# Master.net
KiCad netlist of a schematic drawn in Altium Designer
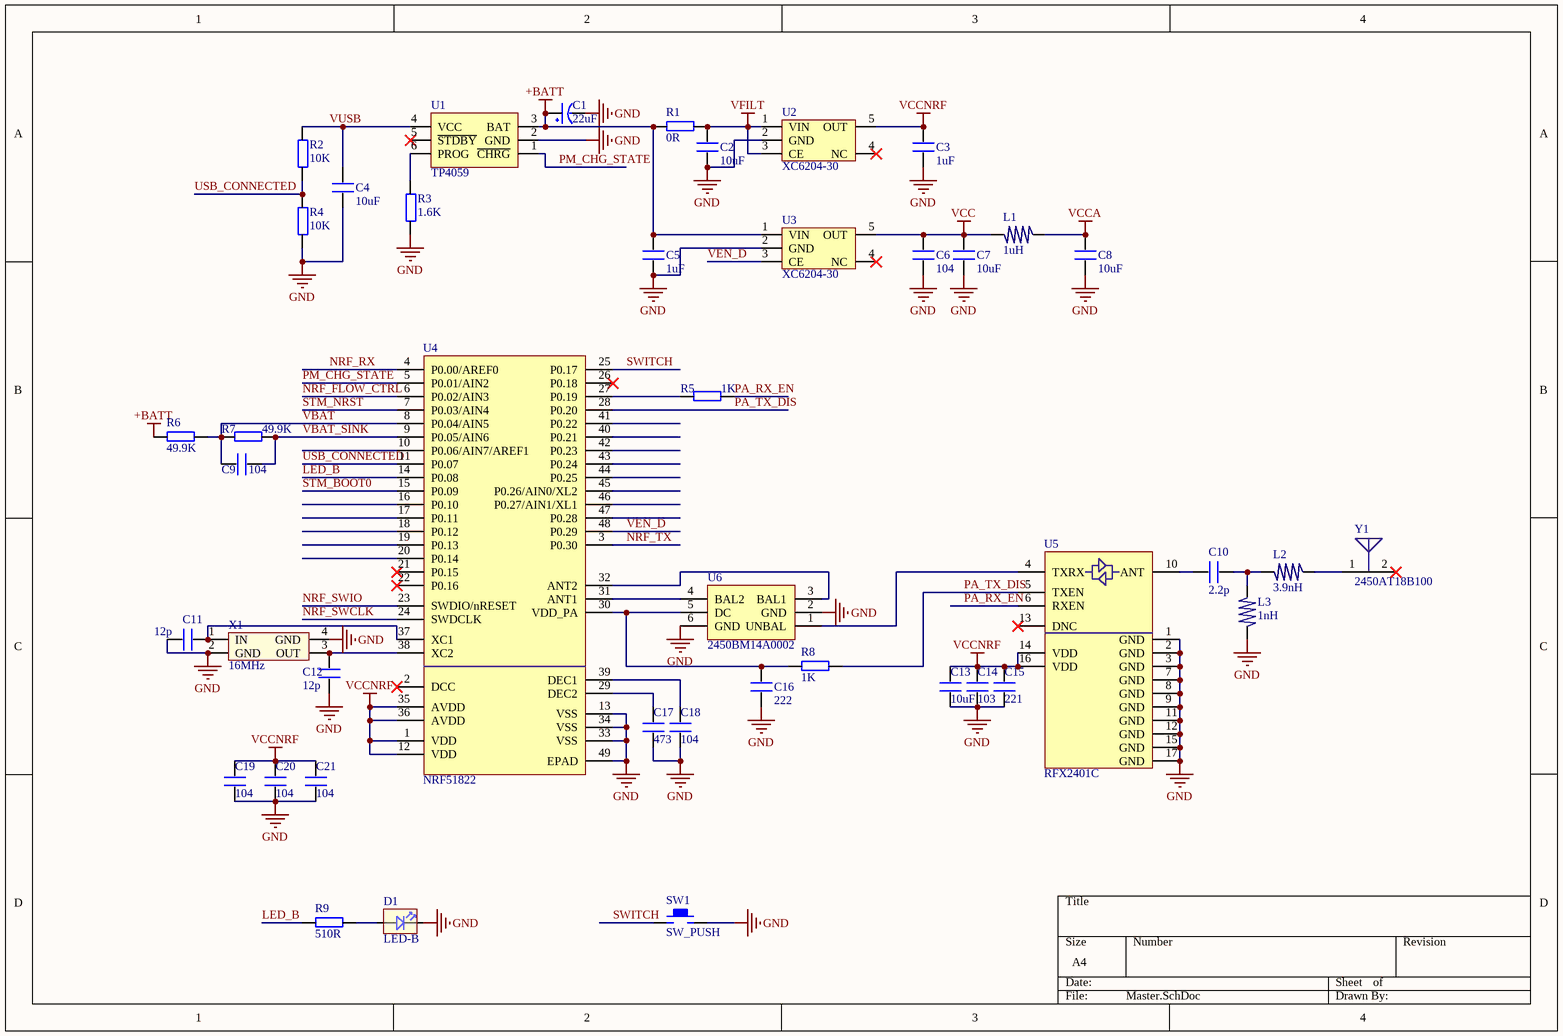
[diagram p0: Master.SchDoc]

(export (version "E")
  (design (tool "Eeschema 10.0.6"))
  (components
    (comp (ref "C1") (value "22uF") (footprint "C0805 钽电容") (libsource (lib "MiniFly ") (part "CAP")))
    (comp (ref "C2") (value "10uF") (footprint "0603P") (libsource (lib "MiniFly ") (part "C")))
    (comp (ref "C3") (value "1uF") (footprint "0402") (libsource (lib "MiniFly ") (part "C")))
    (comp (ref "C4") (value "10uF") (footprint "0603P") (libsource (lib "MiniFly ") (part "C")))
    (comp (ref "C5") (value "1uF") (footprint "0402") (libsource (lib "MiniFly ") (part "C")))
    (comp (ref "C6") (value "104") (footprint "0402") (libsource (lib "MiniFly ") (part "C")))
    (comp (ref "C7") (value "10uF") (footprint "0603P") (libsource (lib "MiniFly ") (part "C")))
    (comp (ref "C8") (value "10uF") (footprint "0603P") (libsource (lib "MiniFly ") (part "C")))
    (comp (ref "C9") (value "104") (footprint "0402") (libsource (lib "MiniFly ") (part "C")))
    (comp (ref "C10") (value "2.2p") (footprint "0402") (libsource (lib "MiniFly ") (part "C")))
    (comp (ref "C11") (value "12p") (footprint "0402") (libsource (lib "MiniFly ") (part "C")))
    (comp (ref "C12") (value "12p") (footprint "0402") (libsource (lib "MiniFly ") (part "C")))
    (comp (ref "C13") (value "10uF") (footprint "0603P") (libsource (lib "MiniFly ") (part "C")))
    (comp (ref "C14") (value "103") (footprint "0402") (libsource (lib "MiniFly ") (part "C")))
    (comp (ref "C15") (value "221") (footprint "0402") (libsource (lib "MiniFly ") (part "C")))
    (comp (ref "C16") (value "222") (footprint "0402") (libsource (lib "MiniFly ") (part "C")))
    (comp (ref "C17") (value "473") (footprint "0402") (libsource (lib "MiniFly ") (part "C")))
    (comp (ref "C18") (value "104") (footprint "0402") (libsource (lib "MiniFly ") (part "C")))
    (comp (ref "C19") (value "104") (footprint "0402") (libsource (lib "MiniFly ") (part "C")))
    (comp (ref "C20") (value "104") (footprint "0402") (libsource (lib "MiniFly ") (part "C")))
    (comp (ref "C21") (value "104") (footprint "0402") (libsource (lib "MiniFly ") (part "C")))
    (comp (ref "D1")
      (value "LED-B")
      (footprint "LED1206  侧贴")
      (description "LED 1206 侧贴  单色")
      (libsource (lib "MiniFly ") (part "LED 1206 侧贴  单色"))
    )
    (comp (ref "L1") (value "1uH") (footprint "0603P") (libsource (lib "") (part "L_1")))
    (comp (ref "L2") (value "3.9nH") (footprint "0603P") (libsource (lib "") (part "L_1")))
    (comp (ref "L3") (value "1nH") (footprint "0603P") (libsource (lib "MiniFly ") (part "L")))
    (comp (ref "R1") (value "0R") (footprint "0402") (libsource (lib "MiniFly ") (part "R")))
    (comp (ref "R2") (value "10K") (footprint "0402") (libsource (lib "MiniFly ") (part "R")))
    (comp (ref "R3") (value "1.6K") (footprint "0402") (libsource (lib "MiniFly ") (part "R")))
    (comp (ref "R4") (value "10K") (footprint "0402") (libsource (lib "MiniFly ") (part "R")))
    (comp (ref "R5") (value "1K") (footprint "0402") (libsource (lib "MiniFly ") (part "R")))
    (comp (ref "R6") (value "49.9K") (footprint "0402") (libsource (lib "MiniFly ") (part "R")))
    (comp (ref "R7") (value "49.9K") (footprint "0402") (libsource (lib "MiniFly ") (part "R")))
    (comp (ref "R8") (value "1K") (footprint "0402") (libsource (lib "MiniFly ") (part "R")))
    (comp (ref "R9") (value "510R") (footprint "0402") (libsource (lib "MiniFly ") (part "R")))
    (comp (ref "SW1") (value "SW_PUSH") (footprint "KEY_2S") (libsource (lib "MiniFly ") (part "KEY")))
    (comp (ref "U1") (value "TP4059") (footprint "SOT23-6S") (libsource (lib "MiniFly ") (part "TP4059")))
    (comp (ref "U2") (value "XC6204-30") (footprint "SOT23-5S") (libsource (lib "MiniFly ") (part "XC6204")))
    (comp (ref "U3") (value "XC6204-30") (footprint "SOT23-5S") (libsource (lib "MiniFly ") (part "XC6204")))
    (comp (ref "U4")
      (value "NRF51822")
      (footprint "QFN48M-04")
      (libsource (lib "MiniFly ") (part "NRF51822"))
    )
    (comp (ref "U5") (value "RFX2401C") (footprint "QFN16M") (libsource (lib "MiniFly ") (part "RFX2401C")))
    (comp (ref "U6") (value "2450BM14A0002") (footprint "0603-6") (libsource (lib "MiniFly ") (part "BALUN")))
    (comp (ref "X1")
      (value "16MHz")
      (footprint "XTAL3225   无源")
      (description "无源贴片晶振")
      (libsource (lib "MiniFly ") (part "XTAL-无源贴片"))
    )
    (comp (ref "Y1")
      (value "2450AT18B100")
      (footprint "1206")
      (libsource (lib "MiniFly ") (part "CHIP_ANTENNA"))
    )
  )
  (nets
    (net (code "1") (name "+BATT") (class "Default")
      (node (ref "C1") (pin "1") (pinfunction "VCC_1") (pintype "passive"))
      (node (ref "C5") (pin "2") (pintype "passive"))
      (node (ref "R1") (pin "2") (pintype "passive"))
      (node (ref "R6") (pin "2") (pintype "passive"))
      (node (ref "U1") (pin "3") (pinfunction "BAT_3") (pintype "passive"))
      (node (ref "U3") (pin "1") (pinfunction "VIN_1") (pintype "passive"))
    )
    (net (code "2") (name "/LED_B") (class "Default")
      (node (ref "R9") (pin "2") (pintype "passive"))
      (node (ref "U4") (pin "14") (pinfunction "P0.08_14") (pintype "passive"))
    )
    (net (code "3") (name "/NRF_FLOW_CTRL") (class "Default")
      (node (ref "U4") (pin "6") (pinfunction "P0.02/AIN3_6") (pintype "passive"))
    )
    (net (code "4") (name "/NRF_RX") (class "Default")
      (node (ref "U4") (pin "4") (pinfunction "P0.00/AREF0_4") (pintype "passive"))
    )
    (net (code "5") (name "/NRF_SWCLK") (class "Default")
      (node (ref "U4") (pin "24") (pinfunction "SWDCLK_24") (pintype "passive"))
    )
    (net (code "6") (name "/NRF_SWIO") (class "Default")
      (node (ref "U4") (pin "23") (pinfunction "SWDIO/nRESET_23") (pintype "passive"))
    )
    (net (code "7") (name "/NRF_TX") (class "Default")
      (node (ref "U4") (pin "3") (pinfunction "P0.30_3") (pintype "passive"))
    )
    (net (code "8") (name "/PA_RX_EN") (class "Default")
      (node (ref "R5") (pin "1") (pintype "passive"))
      (node (ref "U5") (pin "6") (pinfunction "RXEN_6") (pintype "passive"))
    )
    (net (code "9") (name "/PA_TX_DIS") (class "Default")
      (node (ref "R8") (pin "1") (pintype "passive"))
      (node (ref "U4") (pin "28") (pinfunction "P0.20_28") (pintype "passive"))
      (node (ref "U5") (pin "5") (pinfunction "TXEN_5") (pintype "passive"))
    )
    (net (code "10") (name "/PM_CHG_STATE") (class "Default")
      (node (ref "U1") (pin "1") (pinfunction "~{CHRG}_1") (pintype "passive"))
      (node (ref "U4") (pin "5") (pinfunction "P0.01/AIN2_5") (pintype "passive"))
    )
    (net (code "11") (name "/STM_BOOT0") (class "Default")
      (node (ref "U4") (pin "15") (pinfunction "P0.09_15") (pintype "passive"))
    )
    (net (code "12") (name "/STM_NRST") (class "Default")
      (node (ref "U4") (pin "7") (pinfunction "P0.03/AIN4_7") (pintype "passive"))
    )
    (net (code "13") (name "/SWITCH") (class "Default")
      (node (ref "SW1") (pin "1") (pinfunction "1_1") (pintype "passive"))
      (node (ref "U4") (pin "25") (pinfunction "P0.17_25") (pintype "passive"))
    )
    (net (code "14") (name "/USB_CONNECTED") (class "Default")
      (node (ref "R2") (pin "1") (pintype "passive"))
      (node (ref "R4") (pin "2") (pintype "passive"))
      (node (ref "U4") (pin "11") (pinfunction "P0.07_11") (pintype "passive"))
    )
    (net (code "15") (name "/VBAT") (class "Default")
      (node (ref "C9") (pin "2") (pintype "passive"))
      (node (ref "R6") (pin "1") (pintype "passive"))
      (node (ref "R7") (pin "2") (pintype "passive"))
      (node (ref "U4") (pin "8") (pinfunction "P0.04/AIN5_8") (pintype "passive"))
    )
    (net (code "16") (name "/VBAT_SINK") (class "Default")
      (node (ref "C9") (pin "1") (pintype "passive"))
      (node (ref "R7") (pin "1") (pintype "passive"))
      (node (ref "U4") (pin "9") (pinfunction "P0.05/AIN6_9") (pintype "passive"))
    )
    (net (code "17") (name "/VEN_D") (class "Default")
      (node (ref "U3") (pin "3") (pinfunction "CE_3") (pintype "passive"))
      (node (ref "U4") (pin "48") (pinfunction "P0.29_48") (pintype "passive"))
    )
    (net (code "18") (name "/VUSB") (class "Default")
      (node (ref "C4") (pin "2") (pintype "passive"))
      (node (ref "R2") (pin "2") (pintype "passive"))
      (node (ref "U1") (pin "4") (pinfunction "VCC_4") (pintype "passive"))
    )
    (net (code "19") (name "GND") (class "Default")
      (node (ref "C1") (pin "2") (pinfunction "GND_2") (pintype "passive"))
      (node (ref "C11") (pin "2") (pintype "passive"))
      (node (ref "C12") (pin "2") (pintype "passive"))
      (node (ref "C13") (pin "2") (pintype "passive"))
      (node (ref "C14") (pin "2") (pintype "passive"))
      (node (ref "C15") (pin "2") (pintype "passive"))
      (node (ref "C16") (pin "2") (pintype "passive"))
      (node (ref "C17") (pin "2") (pintype "passive"))
      (node (ref "C18") (pin "2") (pintype "passive"))
      (node (ref "C19") (pin "2") (pintype "passive"))
      (node (ref "C2") (pin "1") (pintype "passive"))
      (node (ref "C20") (pin "2") (pintype "passive"))
      (node (ref "C21") (pin "2") (pintype "passive"))
      (node (ref "C3") (pin "1") (pintype "passive"))
      (node (ref "C4") (pin "1") (pintype "passive"))
      (node (ref "C5") (pin "1") (pintype "passive"))
      (node (ref "C6") (pin "1") (pintype "passive"))
      (node (ref "C7") (pin "1") (pintype "passive"))
      (node (ref "C8") (pin "1") (pintype "passive"))
      (node (ref "D1") (pin "1") (pinfunction "1_1") (pintype "passive"))
      (node (ref "L3") (pin "2") (pintype "passive"))
      (node (ref "R3") (pin "1") (pintype "passive"))
      (node (ref "R4") (pin "1") (pintype "passive"))
      (node (ref "SW1") (pin "2") (pinfunction "2_2") (pintype "passive"))
      (node (ref "U1") (pin "2") (pinfunction "GND_2") (pintype "passive"))
      (node (ref "U2") (pin "2") (pinfunction "GND_2") (pintype "passive"))
      (node (ref "U3") (pin "2") (pinfunction "GND_2") (pintype "passive"))
      (node (ref "U4") (pin "13") (pinfunction "VSS_13") (pintype "passive"))
      (node (ref "U4") (pin "33") (pinfunction "VSS_33") (pintype "passive"))
      (node (ref "U4") (pin "34") (pinfunction "VSS_34") (pintype "passive"))
      (node (ref "U4") (pin "49") (pinfunction "EPAD_49") (pintype "passive"))
      (node (ref "U5") (pin "1") (pinfunction "GND_1") (pintype "passive"))
      (node (ref "U5") (pin "11") (pinfunction "GND_11") (pintype "passive"))
      (node (ref "U5") (pin "12") (pinfunction "GND_12") (pintype "passive"))
      (node (ref "U5") (pin "15") (pinfunction "GND_15") (pintype "passive"))
      (node (ref "U5") (pin "17") (pinfunction "GND_17") (pintype "passive"))
      (node (ref "U5") (pin "2") (pinfunction "GND_2") (pintype "passive"))
      (node (ref "U5") (pin "3") (pinfunction "GND_3") (pintype "passive"))
      (node (ref "U5") (pin "7") (pinfunction "GND_7") (pintype "passive"))
      (node (ref "U5") (pin "8") (pinfunction "GND_8") (pintype "passive"))
      (node (ref "U5") (pin "9") (pinfunction "GND_9") (pintype "passive"))
      (node (ref "U6") (pin "2") (pinfunction "GND_2") (pintype "passive"))
      (node (ref "U6") (pin "6") (pinfunction "GND_6") (pintype "passive"))
      (node (ref "X1") (pin "2") (pinfunction "GND_2") (pintype "passive"))
      (node (ref "X1") (pin "4") (pinfunction "GND_4") (pintype "passive"))
    )
    (net (code "20") (name "Net-(C10-Pad2)") (class "Default")
      (node (ref "C10") (pin "2") (pintype "passive"))
      (node (ref "L2") (pin "2") (pintype "passive"))
      (node (ref "L3") (pin "1") (pintype "passive"))
    )
    (net (code "21") (name "Net-(D1-Pad3)") (class "Default")
      (node (ref "D1") (pin "3") (pinfunction "3_3") (pintype "passive"))
      (node (ref "R9") (pin "1") (pintype "passive"))
    )
    (net (code "22") (name "Net-(U1-PROG)") (class "Default")
      (node (ref "R3") (pin "2") (pintype "passive"))
      (node (ref "U1") (pin "6") (pinfunction "PROG_6") (pintype "passive"))
    )
    (net (code "23") (name "Net-(U4-ANT1)") (class "Default")
      (node (ref "U4") (pin "31") (pinfunction "ANT1_31") (pintype "passive"))
      (node (ref "U6") (pin "4") (pinfunction "BAL2_4") (pintype "passive"))
    )
    (net (code "24") (name "Net-(U4-ANT2)") (class "Default")
      (node (ref "U4") (pin "32") (pinfunction "ANT2_32") (pintype "passive"))
      (node (ref "U6") (pin "3") (pinfunction "BAL1_3") (pintype "passive"))
    )
    (net (code "25") (name "Net-(U4-DEC1)") (class "Default")
      (node (ref "C18") (pin "1") (pintype "passive"))
      (node (ref "U4") (pin "39") (pinfunction "DEC1_39") (pintype "passive"))
    )
    (net (code "26") (name "Net-(U4-DEC2)") (class "Default")
      (node (ref "C17") (pin "1") (pintype "passive"))
      (node (ref "U4") (pin "29") (pinfunction "DEC2_29") (pintype "passive"))
    )
    (net (code "27") (name "Net-(U4-P0.19)") (class "Default")
      (node (ref "R5") (pin "2") (pintype "passive"))
      (node (ref "U4") (pin "27") (pinfunction "P0.19_27") (pintype "passive"))
    )
    (net (code "28") (name "Net-(U4-VDD_PA)") (class "Default")
      (node (ref "C16") (pin "1") (pintype "passive"))
      (node (ref "R8") (pin "2") (pintype "passive"))
      (node (ref "U4") (pin "30") (pinfunction "VDD_PA_30") (pintype "passive"))
      (node (ref "U6") (pin "5") (pinfunction "DC_5") (pintype "passive"))
    )
    (net (code "29") (name "Net-(U4-XC1)") (class "Default")
      (node (ref "C11") (pin "1") (pintype "passive"))
      (node (ref "U4") (pin "37") (pinfunction "XC1_37") (pintype "passive"))
      (node (ref "X1") (pin "1") (pinfunction "IN_1") (pintype "passive"))
    )
    (net (code "30") (name "Net-(U4-XC2)") (class "Default")
      (node (ref "C12") (pin "1") (pintype "passive"))
      (node (ref "U4") (pin "38") (pinfunction "XC2_38") (pintype "passive"))
      (node (ref "X1") (pin "3") (pinfunction "OUT_3") (pintype "passive"))
    )
    (net (code "31") (name "Net-(U5-ANT)") (class "Default")
      (node (ref "C10") (pin "1") (pintype "passive"))
      (node (ref "U5") (pin "10") (pinfunction "ANT_10") (pintype "passive"))
    )
    (net (code "32") (name "Net-(U5-TXRX)") (class "Default")
      (node (ref "U5") (pin "4") (pinfunction "TXRX_4") (pintype "passive"))
      (node (ref "U6") (pin "1") (pinfunction "UNBAL_1") (pintype "passive"))
    )
    (net (code "33") (name "Net-(Y1-FP)") (class "Default")
      (node (ref "L2") (pin "1") (pintype "passive"))
      (node (ref "Y1") (pin "1") (pinfunction "FP_1") (pintype "passive"))
    )
    (net (code "34") (name "VCC") (class "Default")
      (node (ref "C6") (pin "2") (pintype "passive"))
      (node (ref "C7") (pin "2") (pintype "passive"))
      (node (ref "L1") (pin "2") (pintype "passive"))
      (node (ref "U3") (pin "5") (pinfunction "OUT_5") (pintype "passive"))
    )
    (net (code "35") (name "VCCA") (class "Default")
      (node (ref "C8") (pin "2") (pintype "passive"))
      (node (ref "L1") (pin "1") (pintype "passive"))
    )
    (net (code "36") (name "VCCNRF") (class "Default")
      (node (ref "C13") (pin "1") (pintype "passive"))
      (node (ref "C14") (pin "1") (pintype "passive"))
      (node (ref "C15") (pin "1") (pintype "passive"))
      (node (ref "C19") (pin "1") (pintype "passive"))
      (node (ref "C20") (pin "1") (pintype "passive"))
      (node (ref "C21") (pin "1") (pintype "passive"))
      (node (ref "C3") (pin "2") (pintype "passive"))
      (node (ref "U2") (pin "5") (pinfunction "OUT_5") (pintype "passive"))
      (node (ref "U4") (pin "1") (pinfunction "VDD_1") (pintype "passive"))
      (node (ref "U4") (pin "12") (pinfunction "VDD_12") (pintype "passive"))
      (node (ref "U4") (pin "35") (pinfunction "AVDD_35") (pintype "passive"))
      (node (ref "U4") (pin "36") (pinfunction "AVDD_36") (pintype "passive"))
      (node (ref "U5") (pin "14") (pinfunction "VDD_14") (pintype "passive"))
      (node (ref "U5") (pin "16") (pinfunction "VDD_16") (pintype "passive"))
    )
    (net (code "37") (name "VFILT") (class "Default")
      (node (ref "C2") (pin "2") (pintype "passive"))
      (node (ref "R1") (pin "1") (pintype "passive"))
      (node (ref "U2") (pin "1") (pinfunction "VIN_1") (pintype "passive"))
      (node (ref "U2") (pin "3") (pinfunction "CE_3") (pintype "passive"))
    )
    (net (code "38") (name "unconnected-(D1-Pad2)") (class "Default")
      (node (ref "D1") (pin "2") (pinfunction "2_2") (pintype "passive"))
    )
    (net (code "39") (name "unconnected-(U1-~{STDBY}-Pad5)") (class "Default")
      (node (ref "U1") (pin "5") (pinfunction "~{STDBY}_5") (pintype "passive+no_connect"))
    )
    (net (code "40") (name "unconnected-(U2-NC-Pad4)") (class "Default")
      (node (ref "U2") (pin "4") (pinfunction "NC_4") (pintype "passive+no_connect"))
    )
    (net (code "41") (name "unconnected-(U3-NC-Pad4)") (class "Default")
      (node (ref "U3") (pin "4") (pinfunction "NC_4") (pintype "passive+no_connect"))
    )
    (net (code "42") (name "unconnected-(U4-DCC-Pad2)") (class "Default")
      (node (ref "U4") (pin "2") (pinfunction "DCC_2") (pintype "passive+no_connect"))
    )
    (net (code "43") (name "unconnected-(U4-P0.06{slash}AIN7{slash}AREF1-Pad10)") (class "Default")
      (node (ref "U4") (pin "10") (pinfunction "P0.06/AIN7/AREF1_10") (pintype "passive"))
    )
    (net (code "44") (name "unconnected-(U4-P0.10-Pad16)") (class "Default")
      (node (ref "U4") (pin "16") (pinfunction "P0.10_16") (pintype "passive"))
    )
    (net (code "45") (name "unconnected-(U4-P0.11-Pad17)") (class "Default")
      (node (ref "U4") (pin "17") (pinfunction "P0.11_17") (pintype "passive"))
    )
    (net (code "46") (name "unconnected-(U4-P0.12-Pad18)") (class "Default")
      (node (ref "U4") (pin "18") (pinfunction "P0.12_18") (pintype "passive"))
    )
    (net (code "47") (name "unconnected-(U4-P0.13-Pad19)") (class "Default")
      (node (ref "U4") (pin "19") (pinfunction "P0.13_19") (pintype "passive"))
    )
    (net (code "48") (name "unconnected-(U4-P0.14-Pad20)") (class "Default")
      (node (ref "U4") (pin "20") (pinfunction "P0.14_20") (pintype "passive"))
    )
    (net (code "49") (name "unconnected-(U4-P0.15-Pad21)") (class "Default")
      (node (ref "U4") (pin "21") (pinfunction "P0.15_21") (pintype "passive+no_connect"))
    )
    (net (code "50") (name "unconnected-(U4-P0.16-Pad22)") (class "Default")
      (node (ref "U4") (pin "22") (pinfunction "P0.16_22") (pintype "passive+no_connect"))
    )
    (net (code "51") (name "unconnected-(U4-P0.18-Pad26)") (class "Default")
      (node (ref "U4") (pin "26") (pinfunction "P0.18_26") (pintype "passive+no_connect"))
    )
    (net (code "52") (name "unconnected-(U4-P0.21-Pad40)") (class "Default")
      (node (ref "U4") (pin "40") (pinfunction "P0.21_40") (pintype "passive"))
    )
    (net (code "53") (name "unconnected-(U4-P0.22-Pad41)") (class "Default")
      (node (ref "U4") (pin "41") (pinfunction "P0.22_41") (pintype "passive"))
    )
    (net (code "54") (name "unconnected-(U4-P0.23-Pad42)") (class "Default")
      (node (ref "U4") (pin "42") (pinfunction "P0.23_42") (pintype "passive"))
    )
    (net (code "55") (name "unconnected-(U4-P0.24-Pad43)") (class "Default")
      (node (ref "U4") (pin "43") (pinfunction "P0.24_43") (pintype "passive"))
    )
    (net (code "56") (name "unconnected-(U4-P0.25-Pad44)") (class "Default")
      (node (ref "U4") (pin "44") (pinfunction "P0.25_44") (pintype "passive"))
    )
    (net (code "57") (name "unconnected-(U4-P0.26{slash}AIN0{slash}XL2-Pad45)") (class "Default")
      (node (ref "U4") (pin "45") (pinfunction "P0.26/AIN0/XL2_45") (pintype "passive"))
    )
    (net (code "58") (name "unconnected-(U4-P0.27{slash}AIN1{slash}XL1-Pad46)") (class "Default")
      (node (ref "U4") (pin "46") (pinfunction "P0.27/AIN1/XL1_46") (pintype "passive"))
    )
    (net (code "59") (name "unconnected-(U4-P0.28-Pad47)") (class "Default")
      (node (ref "U4") (pin "47") (pinfunction "P0.28_47") (pintype "passive"))
    )
    (net (code "60") (name "unconnected-(U5-DNC-Pad13)") (class "Default")
      (node (ref "U5") (pin "13") (pinfunction "DNC_13") (pintype "passive+no_connect"))
    )
    (net (code "61") (name "unconnected-(Y1-NC-Pad2)") (class "Default")
      (node (ref "Y1") (pin "2") (pinfunction "NC_2") (pintype "passive+no_connect"))
    )
  )
)
